# Sheet3.net
KiCad netlist of a schematic drawn in Altium Designer
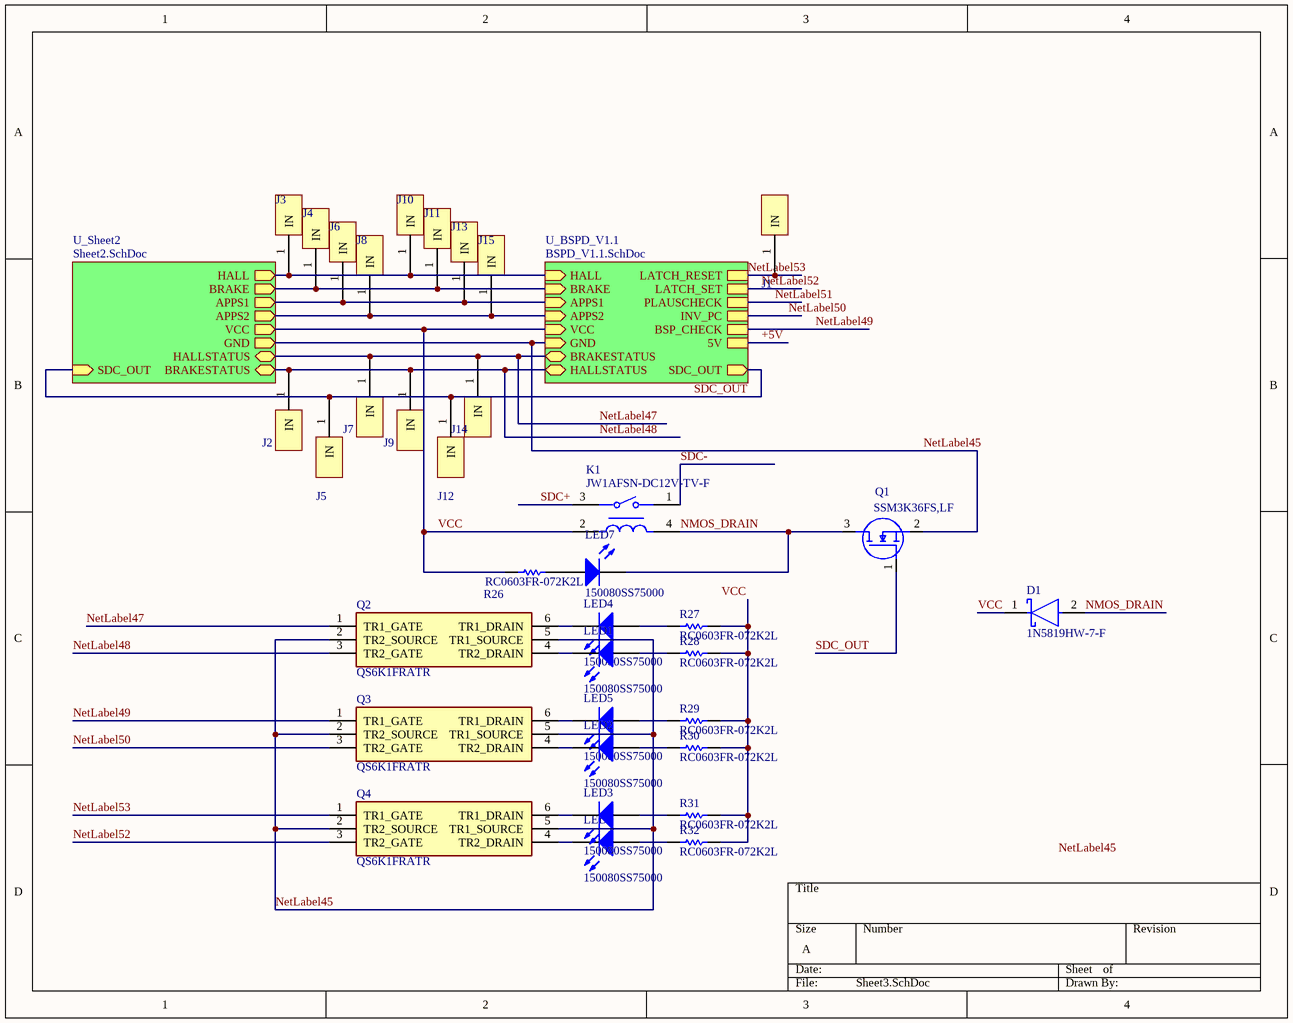
[diagram p0: Sheet3.SchDoc]

(export (version "E")
  (design (tool "Eeschema 10.0.6"))
  (components
    (comp (ref "D1")
      (value "1N5819HW-7-F")
      (footprint "FP-SOD123-IPC_A")
      (description "DIODE SCHOTTKY 40V 1A SOD123")
      (libsource (lib "Altium Content Vault") (part "1d6ec82d83fb6aee721767c19dac4b9"))
    )
    (comp (ref "J1")
      (value "22AWG JUMPER")
      (footprint "22 AWG Hole")
      (libsource (lib "LF50ABDT-TRY") (part "22AWG JUMPER"))
    )
    (comp (ref "J2")
      (value "22AWG JUMPER")
      (footprint "22 AWG Hole")
      (libsource (lib "") (part "22AWG JUMPER_1"))
    )
    (comp (ref "J3")
      (value "22AWG JUMPER")
      (footprint "22 AWG Hole")
      (libsource (lib "LF50ABDT-TRY") (part "22AWG JUMPER"))
    )
    (comp (ref "J4")
      (value "22AWG JUMPER")
      (footprint "22 AWG Hole")
      (libsource (lib "LF50ABDT-TRY") (part "22AWG JUMPER"))
    )
    (comp (ref "J5")
      (value "22AWG JUMPER")
      (footprint "22 AWG Hole")
      (libsource (lib "") (part "22AWG JUMPER_1"))
    )
    (comp (ref "J6")
      (value "22AWG JUMPER")
      (footprint "22 AWG Hole")
      (libsource (lib "LF50ABDT-TRY") (part "22AWG JUMPER"))
    )
    (comp (ref "J7")
      (value "22AWG JUMPER")
      (footprint "22 AWG Hole")
      (libsource (lib "") (part "22AWG JUMPER_1"))
    )
    (comp (ref "J8")
      (value "22AWG JUMPER")
      (footprint "22 AWG Hole")
      (libsource (lib "LF50ABDT-TRY") (part "22AWG JUMPER"))
    )
    (comp (ref "J9")
      (value "22AWG JUMPER")
      (footprint "22 AWG Hole")
      (libsource (lib "") (part "22AWG JUMPER_1"))
    )
    (comp (ref "J10")
      (value "22AWG JUMPER")
      (footprint "22 AWG Hole")
      (libsource (lib "LF50ABDT-TRY") (part "22AWG JUMPER"))
    )
    (comp (ref "J11")
      (value "22AWG JUMPER")
      (footprint "22 AWG Hole")
      (libsource (lib "LF50ABDT-TRY") (part "22AWG JUMPER"))
    )
    (comp (ref "J12")
      (value "22AWG JUMPER")
      (footprint "22 AWG Hole")
      (libsource (lib "") (part "22AWG JUMPER_1"))
    )
    (comp (ref "J13")
      (value "22AWG JUMPER")
      (footprint "22 AWG Hole")
      (libsource (lib "LF50ABDT-TRY") (part "22AWG JUMPER"))
    )
    (comp (ref "J14")
      (value "22AWG JUMPER")
      (footprint "22 AWG Hole")
      (libsource (lib "") (part "22AWG JUMPER_1"))
    )
    (comp (ref "J15")
      (value "22AWG JUMPER")
      (footprint "22 AWG Hole")
      (libsource (lib "LF50ABDT-TRY") (part "22AWG JUMPER"))
    )
    (comp (ref "K1")
      (value "JW1AFSN-DC12V-TV-F")
      (footprint "FP-JW1AFSN-DC12V-TV-F-MFG")
      (description "RELAY GEN PURPOSE SPST 10A 12V")
      (libsource (lib "Altium Content Vault") (part "4a7ea6db6c9d29be3ef62a771ae539b"))
    )
    (comp (ref "LED1")
      (value "150080SS75000")
      (footprint "0805_A")
      (description "SMD mono-color Chip LED, WL-SMCW, Super Red")
      (fields (field (name "MANUFACTURER") "Wuerth Elektronik"))
      (libsource (lib "Altium Content Vault") (part "WE-LED_K1A2-2"))
    )
    (comp (ref "LED2")
      (value "150080SS75000")
      (footprint "0805_A")
      (description "SMD mono-color Chip LED, WL-SMCW, Super Red")
      (fields (field (name "MANUFACTURER") "Wuerth Elektronik"))
      (libsource (lib "Altium Content Vault") (part "WE-LED_K1A2-2"))
    )
    (comp (ref "LED3")
      (value "150080SS75000")
      (footprint "0805_A")
      (description "SMD mono-color Chip LED, WL-SMCW, Super Red")
      (fields (field (name "MANUFACTURER") "Wuerth Elektronik"))
      (libsource (lib "Altium Content Vault") (part "WE-LED_K1A2-2"))
    )
    (comp (ref "LED4")
      (value "150080SS75000")
      (footprint "0805_A")
      (description "SMD mono-color Chip LED, WL-SMCW, Super Red")
      (fields (field (name "MANUFACTURER") "Wuerth Elektronik"))
      (libsource (lib "Altium Content Vault") (part "WE-LED_K1A2-2"))
    )
    (comp (ref "LED5")
      (value "150080SS75000")
      (footprint "0805_A")
      (description "SMD mono-color Chip LED, WL-SMCW, Super Red")
      (fields (field (name "MANUFACTURER") "Wuerth Elektronik"))
      (libsource (lib "Altium Content Vault") (part "WE-LED_K1A2-2"))
    )
    (comp (ref "LED6")
      (value "150080SS75000")
      (footprint "0805_A")
      (description "SMD mono-color Chip LED, WL-SMCW, Super Red")
      (fields (field (name "MANUFACTURER") "Wuerth Elektronik"))
      (libsource (lib "Altium Content Vault") (part "WE-LED_K1A2-2"))
    )
    (comp (ref "LED7")
      (value "150080SS75000")
      (footprint "0805_A")
      (description "SMD mono-color Chip LED, WL-SMCW, Super Red")
      (fields (field (name "MANUFACTURER") "Wuerth Elektronik"))
      (libsource (lib "Altium Content Vault") (part "WE-LED_K1A2-2"))
    )
    (comp (ref "Q1")
      (value "SSM3K36FS,LF")
      (footprint "SamacSys:1SS423")
      (description "MOSFET (N-Channel)")
      (fields (field (name "MOUSER PART NUMBER") "757-SSM3K36FSLF"))
      (libsource (lib "*") (part "SSM3K36FS,LF"))
    )
    (comp (ref "Q2")
      (value "QS6K1FRATR")
      (footprint "SamacSys:SOT95P280X100-6N")
      (description "MOSFET (N-Channel)")
      (fields (field (name "MOUSER PART NUMBER") "755-QS6K1FRATR"))
      (libsource (lib "*") (part "QS6K1FRATR"))
    )
    (comp (ref "Q3")
      (value "QS6K1FRATR")
      (footprint "SamacSys:SOT95P280X100-6N")
      (description "MOSFET (N-Channel)")
      (fields (field (name "MOUSER PART NUMBER") "755-QS6K1FRATR"))
      (libsource (lib "*") (part "QS6K1FRATR"))
    )
    (comp (ref "Q4")
      (value "QS6K1FRATR")
      (footprint "SamacSys:SOT95P280X100-6N")
      (description "MOSFET (N-Channel)")
      (fields (field (name "MOUSER PART NUMBER") "755-QS6K1FRATR"))
      (libsource (lib "*") (part "QS6K1FRATR"))
    )
    (comp (ref "R26")
      (value "RC0603FR-072K2L")
      (footprint "RESC1608X55X25LL10T15")
      (fields (field (name "TOLERANCE") "1%") (field (name "MANUFACTURER") "Yageo"))
      (libsource (lib "Altium Content Vault") (part "RES-2"))
    )
    (comp (ref "R27")
      (value "RC0603FR-072K2L")
      (footprint "RESC1608X55X25LL10T15")
      (fields (field (name "TOLERANCE") "1%") (field (name "MANUFACTURER") "Yageo"))
      (libsource (lib "Altium Content Vault") (part "RES-2"))
    )
    (comp (ref "R28")
      (value "RC0603FR-072K2L")
      (footprint "RESC1608X55X25LL10T15")
      (fields (field (name "TOLERANCE") "1%") (field (name "MANUFACTURER") "Yageo"))
      (libsource (lib "Altium Content Vault") (part "RES-2"))
    )
    (comp (ref "R29")
      (value "RC0603FR-072K2L")
      (footprint "RESC1608X55X25LL10T15")
      (fields (field (name "TOLERANCE") "1%") (field (name "MANUFACTURER") "Yageo"))
      (libsource (lib "Altium Content Vault") (part "RES-2"))
    )
    (comp (ref "R30")
      (value "RC0603FR-072K2L")
      (footprint "RESC1608X55X25LL10T15")
      (fields (field (name "TOLERANCE") "1%") (field (name "MANUFACTURER") "Yageo"))
      (libsource (lib "Altium Content Vault") (part "RES-2"))
    )
    (comp (ref "R31")
      (value "RC0603FR-072K2L")
      (footprint "RESC1608X55X25LL10T15")
      (fields (field (name "TOLERANCE") "1%") (field (name "MANUFACTURER") "Yageo"))
      (libsource (lib "Altium Content Vault") (part "RES-2"))
    )
    (comp (ref "R32")
      (value "RC0603FR-072K2L")
      (footprint "RESC1608X55X25LL10T15")
      (fields (field (name "TOLERANCE") "1%") (field (name "MANUFACTURER") "Yageo"))
      (libsource (lib "Altium Content Vault") (part "RES-2"))
    )
  )
  (nets
    (net (code "2") (name "/APPS1") (class "Default")
      (node (ref "J13") (pin "1") (pinfunction "IN_1") (pintype "passive"))
      (node (ref "J6") (pin "1") (pinfunction "IN_1") (pintype "passive"))
    )
    (net (code "3") (name "/APPS2") (class "Default")
      (node (ref "J15") (pin "1") (pinfunction "IN_1") (pintype "passive"))
      (node (ref "J8") (pin "1") (pinfunction "IN_1") (pintype "passive"))
    )
    (net (code "4") (name "/BRAKE") (class "Default")
      (node (ref "J11") (pin "1") (pinfunction "IN_1") (pintype "passive"))
      (node (ref "J4") (pin "1") (pinfunction "IN_1") (pintype "passive"))
    )
    (net (code "5") (name "/HALL") (class "Default")
      (node (ref "J10") (pin "1") (pinfunction "IN_1") (pintype "passive"))
      (node (ref "J3") (pin "1") (pinfunction "IN_1") (pintype "passive"))
    )
    (net (code "6") (name "/NMOS_DRAIN") (class "Default")
      (node (ref "D1") (pin "2") (pinfunction "A_2") (pintype "passive"))
      (node (ref "K1") (pin "4") (pinfunction "4_4") (pintype "passive"))
      (node (ref "LED7") (pin "1") (pinfunction "K_1") (pintype "passive"))
      (node (ref "Q1") (pin "3") (pinfunction "D_3") (pintype "passive"))
    )
    (net (code "7") (name "/NetLabel45") (class "Default")
      (node (ref "Q1") (pin "2") (pinfunction "S_2") (pintype "passive"))
      (node (ref "Q2") (pin "2") (pinfunction "TR2_SOURCE_2") (pintype "passive"))
      (node (ref "Q2") (pin "5") (pinfunction "TR1_SOURCE_5") (pintype "passive"))
      (node (ref "Q3") (pin "2") (pinfunction "TR2_SOURCE_2") (pintype "passive"))
      (node (ref "Q3") (pin "5") (pinfunction "TR1_SOURCE_5") (pintype "passive"))
      (node (ref "Q4") (pin "2") (pinfunction "TR2_SOURCE_2") (pintype "passive"))
      (node (ref "Q4") (pin "5") (pinfunction "TR1_SOURCE_5") (pintype "passive"))
    )
    (net (code "8") (name "/NetLabel47") (class "Default")
      (node (ref "J14") (pin "1") (pinfunction "IN_1") (pintype "passive"))
      (node (ref "J7") (pin "1") (pinfunction "IN_1") (pintype "passive"))
      (node (ref "Q2") (pin "1") (pinfunction "TR1_GATE_1") (pintype "passive"))
    )
    (net (code "9") (name "/NetLabel48") (class "Default")
      (node (ref "J2") (pin "1") (pinfunction "IN_1") (pintype "passive"))
      (node (ref "J9") (pin "1") (pinfunction "IN_1") (pintype "passive"))
      (node (ref "Q2") (pin "3") (pinfunction "TR2_GATE_3") (pintype "passive"))
    )
    (net (code "10") (name "/NetLabel49") (class "Default")
      (node (ref "Q3") (pin "1") (pinfunction "TR1_GATE_1") (pintype "passive"))
    )
    (net (code "11") (name "/NetLabel50") (class "Default")
      (node (ref "Q3") (pin "3") (pinfunction "TR2_GATE_3") (pintype "passive"))
    )
    (net (code "13") (name "/NetLabel52") (class "Default")
      (node (ref "Q4") (pin "3") (pinfunction "TR2_GATE_3") (pintype "passive"))
    )
    (net (code "14") (name "/NetLabel53") (class "Default")
      (node (ref "J1") (pin "1") (pinfunction "IN_1") (pintype "passive"))
      (node (ref "Q4") (pin "1") (pinfunction "TR1_GATE_1") (pintype "passive"))
    )
    (net (code "15") (name "/SDC+") (class "Default")
      (node (ref "K1") (pin "3") (pinfunction "3_3") (pintype "passive"))
    )
    (net (code "16") (name "/SDC-") (class "Default")
      (node (ref "K1") (pin "1") (pinfunction "1_1") (pintype "passive"))
    )
    (net (code "17") (name "/SDC_OUT") (class "Default")
      (node (ref "J12") (pin "1") (pinfunction "IN_1") (pintype "passive"))
      (node (ref "J5") (pin "1") (pinfunction "IN_1") (pintype "passive"))
      (node (ref "Q1") (pin "1") (pinfunction "G_1") (pintype "passive"))
    )
    (net (code "18") (name "/VCC") (class "Default")
      (node (ref "D1") (pin "1") (pinfunction "C_1") (pintype "passive"))
      (node (ref "K1") (pin "2") (pinfunction "2_2") (pintype "passive"))
      (node (ref "R26") (pin "1") (pinfunction "1_1") (pintype "passive"))
      (node (ref "R27") (pin "2") (pinfunction "2_2") (pintype "passive"))
      (node (ref "R28") (pin "2") (pinfunction "2_2") (pintype "passive"))
      (node (ref "R29") (pin "2") (pinfunction "2_2") (pintype "passive"))
      (node (ref "R30") (pin "2") (pinfunction "2_2") (pintype "passive"))
      (node (ref "R31") (pin "2") (pinfunction "2_2") (pintype "passive"))
      (node (ref "R32") (pin "2") (pinfunction "2_2") (pintype "passive"))
    )
    (net (code "19") (name "Net-(LED1-A)") (class "Default")
      (node (ref "LED1") (pin "2") (pinfunction "A_2") (pintype "passive"))
      (node (ref "R28") (pin "1") (pinfunction "1_1") (pintype "passive"))
    )
    (net (code "20") (name "Net-(LED1-K)") (class "Default")
      (node (ref "LED1") (pin "1") (pinfunction "K_1") (pintype "passive"))
      (node (ref "Q2") (pin "4") (pinfunction "TR2_DRAIN_4") (pintype "passive"))
    )
    (net (code "21") (name "Net-(LED2-A)") (class "Default")
      (node (ref "LED2") (pin "2") (pinfunction "A_2") (pintype "passive"))
      (node (ref "R30") (pin "1") (pinfunction "1_1") (pintype "passive"))
    )
    (net (code "22") (name "Net-(LED2-K)") (class "Default")
      (node (ref "LED2") (pin "1") (pinfunction "K_1") (pintype "passive"))
      (node (ref "Q3") (pin "4") (pinfunction "TR2_DRAIN_4") (pintype "passive"))
    )
    (net (code "23") (name "Net-(LED3-A)") (class "Default")
      (node (ref "LED3") (pin "2") (pinfunction "A_2") (pintype "passive"))
      (node (ref "R31") (pin "1") (pinfunction "1_1") (pintype "passive"))
    )
    (net (code "24") (name "Net-(LED3-K)") (class "Default")
      (node (ref "LED3") (pin "1") (pinfunction "K_1") (pintype "passive"))
      (node (ref "Q4") (pin "6") (pinfunction "TR1_DRAIN_6") (pintype "passive"))
    )
    (net (code "25") (name "Net-(LED4-A)") (class "Default")
      (node (ref "LED4") (pin "2") (pinfunction "A_2") (pintype "passive"))
      (node (ref "R27") (pin "1") (pinfunction "1_1") (pintype "passive"))
    )
    (net (code "26") (name "Net-(LED4-K)") (class "Default")
      (node (ref "LED4") (pin "1") (pinfunction "K_1") (pintype "passive"))
      (node (ref "Q2") (pin "6") (pinfunction "TR1_DRAIN_6") (pintype "passive"))
    )
    (net (code "27") (name "Net-(LED5-A)") (class "Default")
      (node (ref "LED5") (pin "2") (pinfunction "A_2") (pintype "passive"))
      (node (ref "R29") (pin "1") (pinfunction "1_1") (pintype "passive"))
    )
    (net (code "28") (name "Net-(LED5-K)") (class "Default")
      (node (ref "LED5") (pin "1") (pinfunction "K_1") (pintype "passive"))
      (node (ref "Q3") (pin "6") (pinfunction "TR1_DRAIN_6") (pintype "passive"))
    )
    (net (code "29") (name "Net-(LED6-A)") (class "Default")
      (node (ref "LED6") (pin "2") (pinfunction "A_2") (pintype "passive"))
      (node (ref "R32") (pin "1") (pinfunction "1_1") (pintype "passive"))
    )
    (net (code "30") (name "Net-(LED6-K)") (class "Default")
      (node (ref "LED6") (pin "1") (pinfunction "K_1") (pintype "passive"))
      (node (ref "Q4") (pin "4") (pinfunction "TR2_DRAIN_4") (pintype "passive"))
    )
    (net (code "31") (name "Net-(LED7-A)") (class "Default")
      (node (ref "LED7") (pin "2") (pinfunction "A_2") (pintype "passive"))
      (node (ref "R26") (pin "2") (pinfunction "2_2") (pintype "passive"))
    )
  )
)
